# MGMEZZ02.net
KiCad netlist of a schematic drawn in Altium Designer
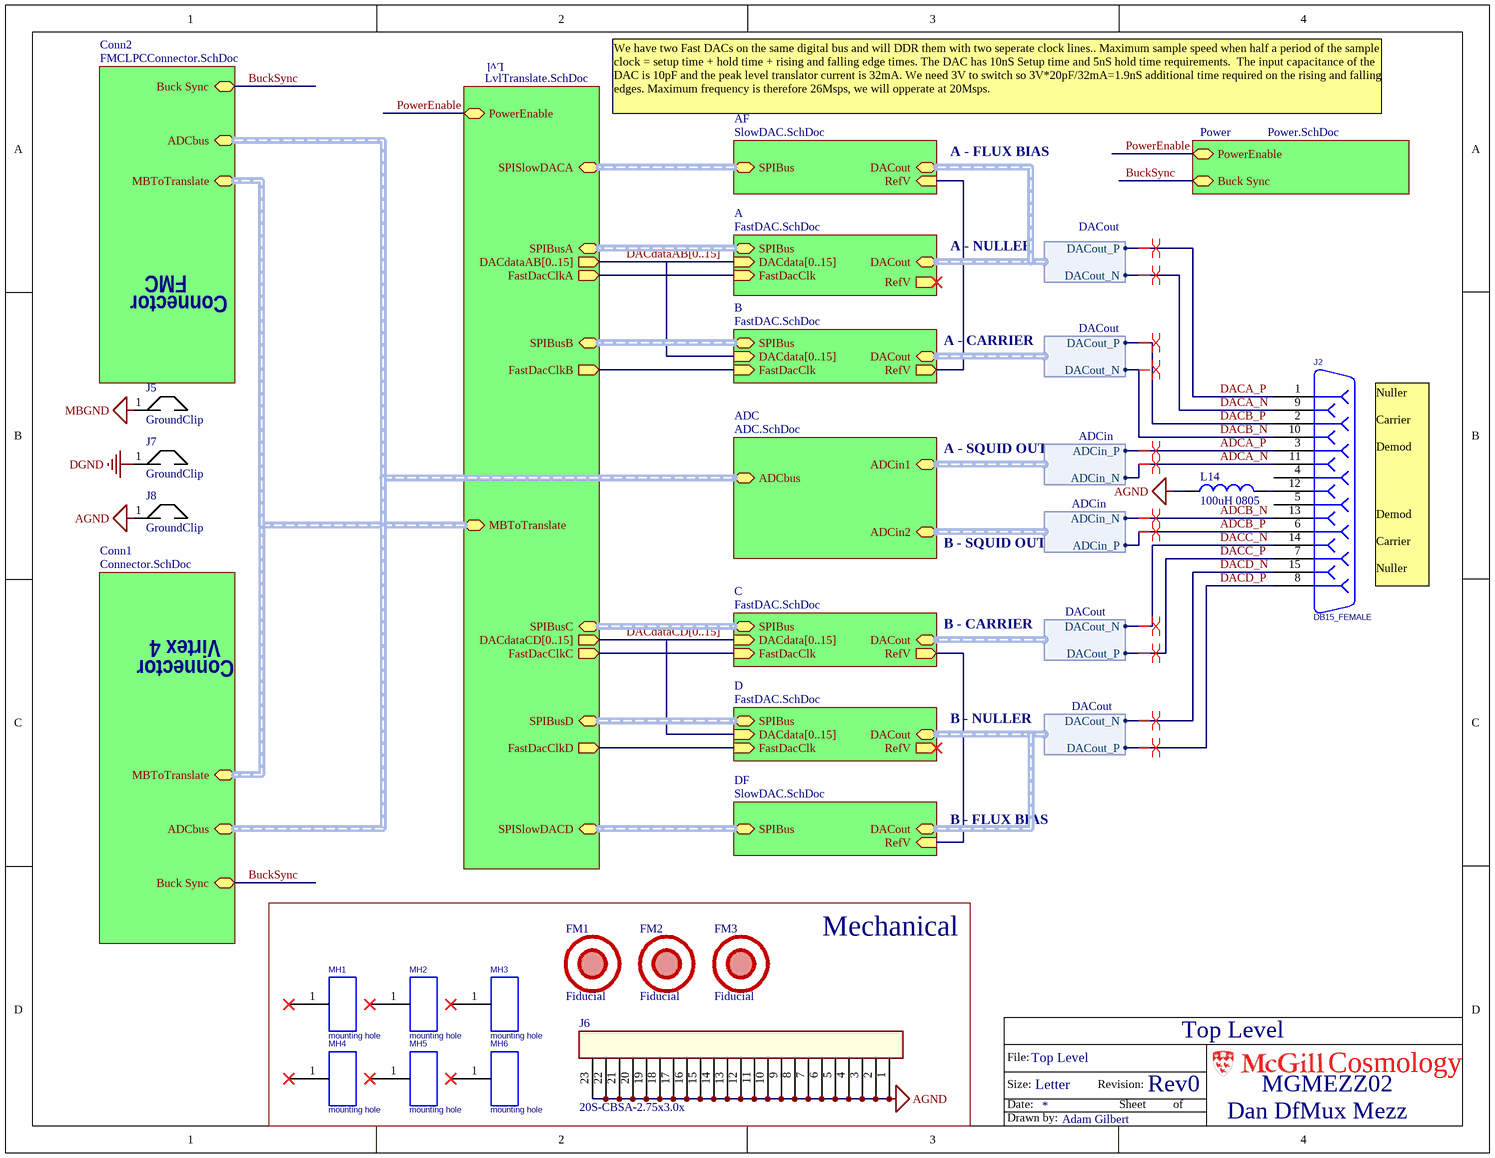
[diagram p0: MGMEZZ02.SchDoc]

(export (version "E")
  (design (tool "Eeschema 10.0.6"))
  (components
    (comp (ref "FM1")
      (value "Fiducial")
      (footprint "Fiducial_mark")
      (libsource (lib "MGMEZZ04") (part "Fiducial"))
    )
    (comp (ref "FM2")
      (value "Fiducial")
      (footprint "Fiducial_mark")
      (libsource (lib "MGMEZZ04") (part "Fiducial"))
    )
    (comp (ref "FM3")
      (value "Fiducial")
      (footprint "Fiducial_mark")
      (libsource (lib "MGMEZZ04") (part "Fiducial"))
    )
    (comp (ref "J2")
      (value "DB15_FEMALE")
      (fields
        (field (name "MANUFACTURERS PART NUMBER") "182-015-213R181")
        (field (name "MANUFACTURER") "Norcomp")
      )
      (libsource (lib "MGMEZZ04") (part "DB15_FEMALE"))
    )
    (comp (ref "J5")
      (value "GroundClip")
      (footprint "GroundClip")
      (description "Ground Clip point")
      (fields
        (field (name "MANUFACTURER") "Keystone Electronics")
        (field (name "MANUFACTURERS PART NUMBER") "5015")
      )
      (libsource (lib "MGMEZZ04") (part "GroundClip"))
    )
    (comp (ref "J6")
      (value "20S-CBSA-2.75x3.0x")
      (footprint "SHIELD 2.75X3.00")
      (libsource (lib "MGMEZZ04") (part "MezzShield"))
    )
    (comp (ref "J7")
      (value "GroundClip")
      (footprint "GroundClip")
      (description "Ground Clip point")
      (fields
        (field (name "MANUFACTURER") "Keystone Electronics")
        (field (name "MANUFACTURERS PART NUMBER") "5015")
      )
      (libsource (lib "MGMEZZ04") (part "GroundClip"))
    )
    (comp (ref "J8")
      (value "GroundClip")
      (footprint "GroundClip")
      (description "Ground Clip point")
      (fields
        (field (name "MANUFACTURER") "Keystone Electronics")
        (field (name "MANUFACTURERS PART NUMBER") "5015")
      )
      (libsource (lib "MGMEZZ04") (part "GroundClip"))
    )
    (comp (ref "L14")
      (value "100uH 0805")
      (footprint "0805")
      (description "Inductor 0805")
      (fields
        (field (name "MANUFACTURER") "TDK Corporation")
        (field (name "MANUFACTURERS PART NUMBER") "GLCR2012T101M-HC")
      )
      (libsource (lib "MGMEZZ04") (part "IND 0805"))
    )
    (comp (ref "MH1") (value "mounting hole") (libsource (lib "MGMEZZ04") (part "MTHOLE")))
    (comp (ref "MH2") (value "mounting hole") (libsource (lib "MGMEZZ04") (part "MTHOLE")))
    (comp (ref "MH3") (value "mounting hole") (libsource (lib "MGMEZZ04") (part "MTHOLE")))
    (comp (ref "MH4") (value "mounting hole") (libsource (lib "MGMEZZ04") (part "MTHOLE")))
    (comp (ref "MH5") (value "mounting hole") (libsource (lib "MGMEZZ04") (part "MTHOLE")))
    (comp (ref "MH6") (value "mounting hole") (libsource (lib "MGMEZZ04") (part "MTHOLE")))
  )
  (nets
    (net (code "35") (name "/ADCA_N") (class "Default")
      (node (ref "J2") (pin "11") (pinfunction "p11_11") (pintype "passive"))
    )
    (net (code "36") (name "/ADCA_P") (class "Default")
      (node (ref "J2") (pin "3") (pinfunction "p3_3") (pintype "passive"))
    )
    (net (code "37") (name "/ADCB_N") (class "Default")
      (node (ref "J2") (pin "13") (pinfunction "p13_13") (pintype "passive"))
    )
    (net (code "38") (name "/ADCB_P") (class "Default")
      (node (ref "J2") (pin "6") (pinfunction "p6_6") (pintype "passive"))
    )
    (net (code "41") (name "/DACA_N") (class "Default")
      (node (ref "J2") (pin "9") (pinfunction "p9_9") (pintype "passive"))
    )
    (net (code "42") (name "/DACA_P") (class "Default")
      (node (ref "J2") (pin "1") (pinfunction "p1_1") (pintype "passive"))
    )
    (net (code "43") (name "/DACB_N") (class "Default")
      (node (ref "J2") (pin "10") (pinfunction "p10_10") (pintype "passive"))
    )
    (net (code "44") (name "/DACB_P") (class "Default")
      (node (ref "J2") (pin "2") (pinfunction "p2_2") (pintype "passive"))
    )
    (net (code "45") (name "/DACC_N") (class "Default")
      (node (ref "J2") (pin "14") (pinfunction "p14_14") (pintype "passive"))
    )
    (net (code "46") (name "/DACC_P") (class "Default")
      (node (ref "J2") (pin "7") (pinfunction "p7_7") (pintype "passive"))
    )
    (net (code "47") (name "/DACD_N") (class "Default")
      (node (ref "J2") (pin "15") (pinfunction "p15_15") (pintype "passive"))
    )
    (net (code "48") (name "/DACD_P") (class "Default")
      (node (ref "J2") (pin "8") (pinfunction "p8_8") (pintype "passive"))
    )
    (net (code "73") (name "AGND") (class "Default")
      (node (ref "J6") (pin "1") (pinfunction "1_1") (pintype "passive"))
      (node (ref "J6") (pin "10") (pinfunction "10_10") (pintype "passive"))
      (node (ref "J6") (pin "11") (pinfunction "11_11") (pintype "passive"))
      (node (ref "J6") (pin "12") (pinfunction "12_12") (pintype "passive"))
      (node (ref "J6") (pin "13") (pinfunction "13_13") (pintype "passive"))
      (node (ref "J6") (pin "14") (pinfunction "14_14") (pintype "passive"))
      (node (ref "J6") (pin "15") (pinfunction "15_15") (pintype "passive"))
      (node (ref "J6") (pin "16") (pinfunction "16_16") (pintype "passive"))
      (node (ref "J6") (pin "17") (pinfunction "17_17") (pintype "passive"))
      (node (ref "J6") (pin "18") (pinfunction "18_18") (pintype "passive"))
      (node (ref "J6") (pin "19") (pinfunction "19_19") (pintype "passive"))
      (node (ref "J6") (pin "2") (pinfunction "2_2") (pintype "passive"))
      (node (ref "J6") (pin "20") (pinfunction "20_20") (pintype "passive"))
      (node (ref "J6") (pin "21") (pinfunction "21_21") (pintype "passive"))
      (node (ref "J6") (pin "22") (pinfunction "22_22") (pintype "passive"))
      (node (ref "J6") (pin "23") (pinfunction "23_23") (pintype "passive"))
      (node (ref "J6") (pin "3") (pinfunction "3_3") (pintype "passive"))
      (node (ref "J6") (pin "4") (pinfunction "4_4") (pintype "passive"))
      (node (ref "J6") (pin "5") (pinfunction "5_5") (pintype "passive"))
      (node (ref "J6") (pin "6") (pinfunction "6_6") (pintype "passive"))
      (node (ref "J6") (pin "7") (pinfunction "7_7") (pintype "passive"))
      (node (ref "J6") (pin "8") (pinfunction "8_8") (pintype "passive"))
      (node (ref "J6") (pin "9") (pinfunction "9_9") (pintype "passive"))
      (node (ref "J8") (pin "1") (pinfunction "1_1") (pintype "passive"))
      (node (ref "L14") (pin "1") (pinfunction "1_1") (pintype "passive"))
    )
    (net (code "74") (name "DGND") (class "Default")
      (node (ref "J7") (pin "1") (pinfunction "1_1") (pintype "passive"))
    )
    (net (code "75") (name "MBGND") (class "Default")
      (node (ref "J5") (pin "1") (pinfunction "1_1") (pintype "passive"))
    )
    (net (code "76") (name "Net-(J2-p12)") (class "Default")
      (node (ref "J2") (pin "12") (pinfunction "p12_12") (pintype "passive"))
      (node (ref "L14") (pin "2") (pinfunction "2_2") (pintype "passive"))
    )
    (net (code "77") (name "unconnected-(J2-p4-Pad4)") (class "Default")
      (node (ref "J2") (pin "4") (pinfunction "p4_4") (pintype "passive"))
    )
    (net (code "78") (name "unconnected-(J2-p5-Pad5)") (class "Default")
      (node (ref "J2") (pin "5") (pinfunction "p5_5") (pintype "passive"))
    )
    (net (code "79") (name "unconnected-(MH1-A-Pad1)") (class "Default")
      (node (ref "MH1") (pin "1") (pinfunction "A_1") (pintype "passive+no_connect"))
    )
    (net (code "80") (name "unconnected-(MH2-A-Pad1)") (class "Default")
      (node (ref "MH2") (pin "1") (pinfunction "A_1") (pintype "passive+no_connect"))
    )
    (net (code "81") (name "unconnected-(MH3-A-Pad1)") (class "Default")
      (node (ref "MH3") (pin "1") (pinfunction "A_1") (pintype "passive+no_connect"))
    )
    (net (code "82") (name "unconnected-(MH4-A-Pad1)") (class "Default")
      (node (ref "MH4") (pin "1") (pinfunction "A_1") (pintype "passive+no_connect"))
    )
    (net (code "83") (name "unconnected-(MH5-A-Pad1)") (class "Default")
      (node (ref "MH5") (pin "1") (pinfunction "A_1") (pintype "passive+no_connect"))
    )
    (net (code "84") (name "unconnected-(MH6-A-Pad1)") (class "Default")
      (node (ref "MH6") (pin "1") (pinfunction "A_1") (pintype "passive+no_connect"))
    )
  )
)
